# 11A-001.net
KiCad netlist of a schematic drawn in EAGLE
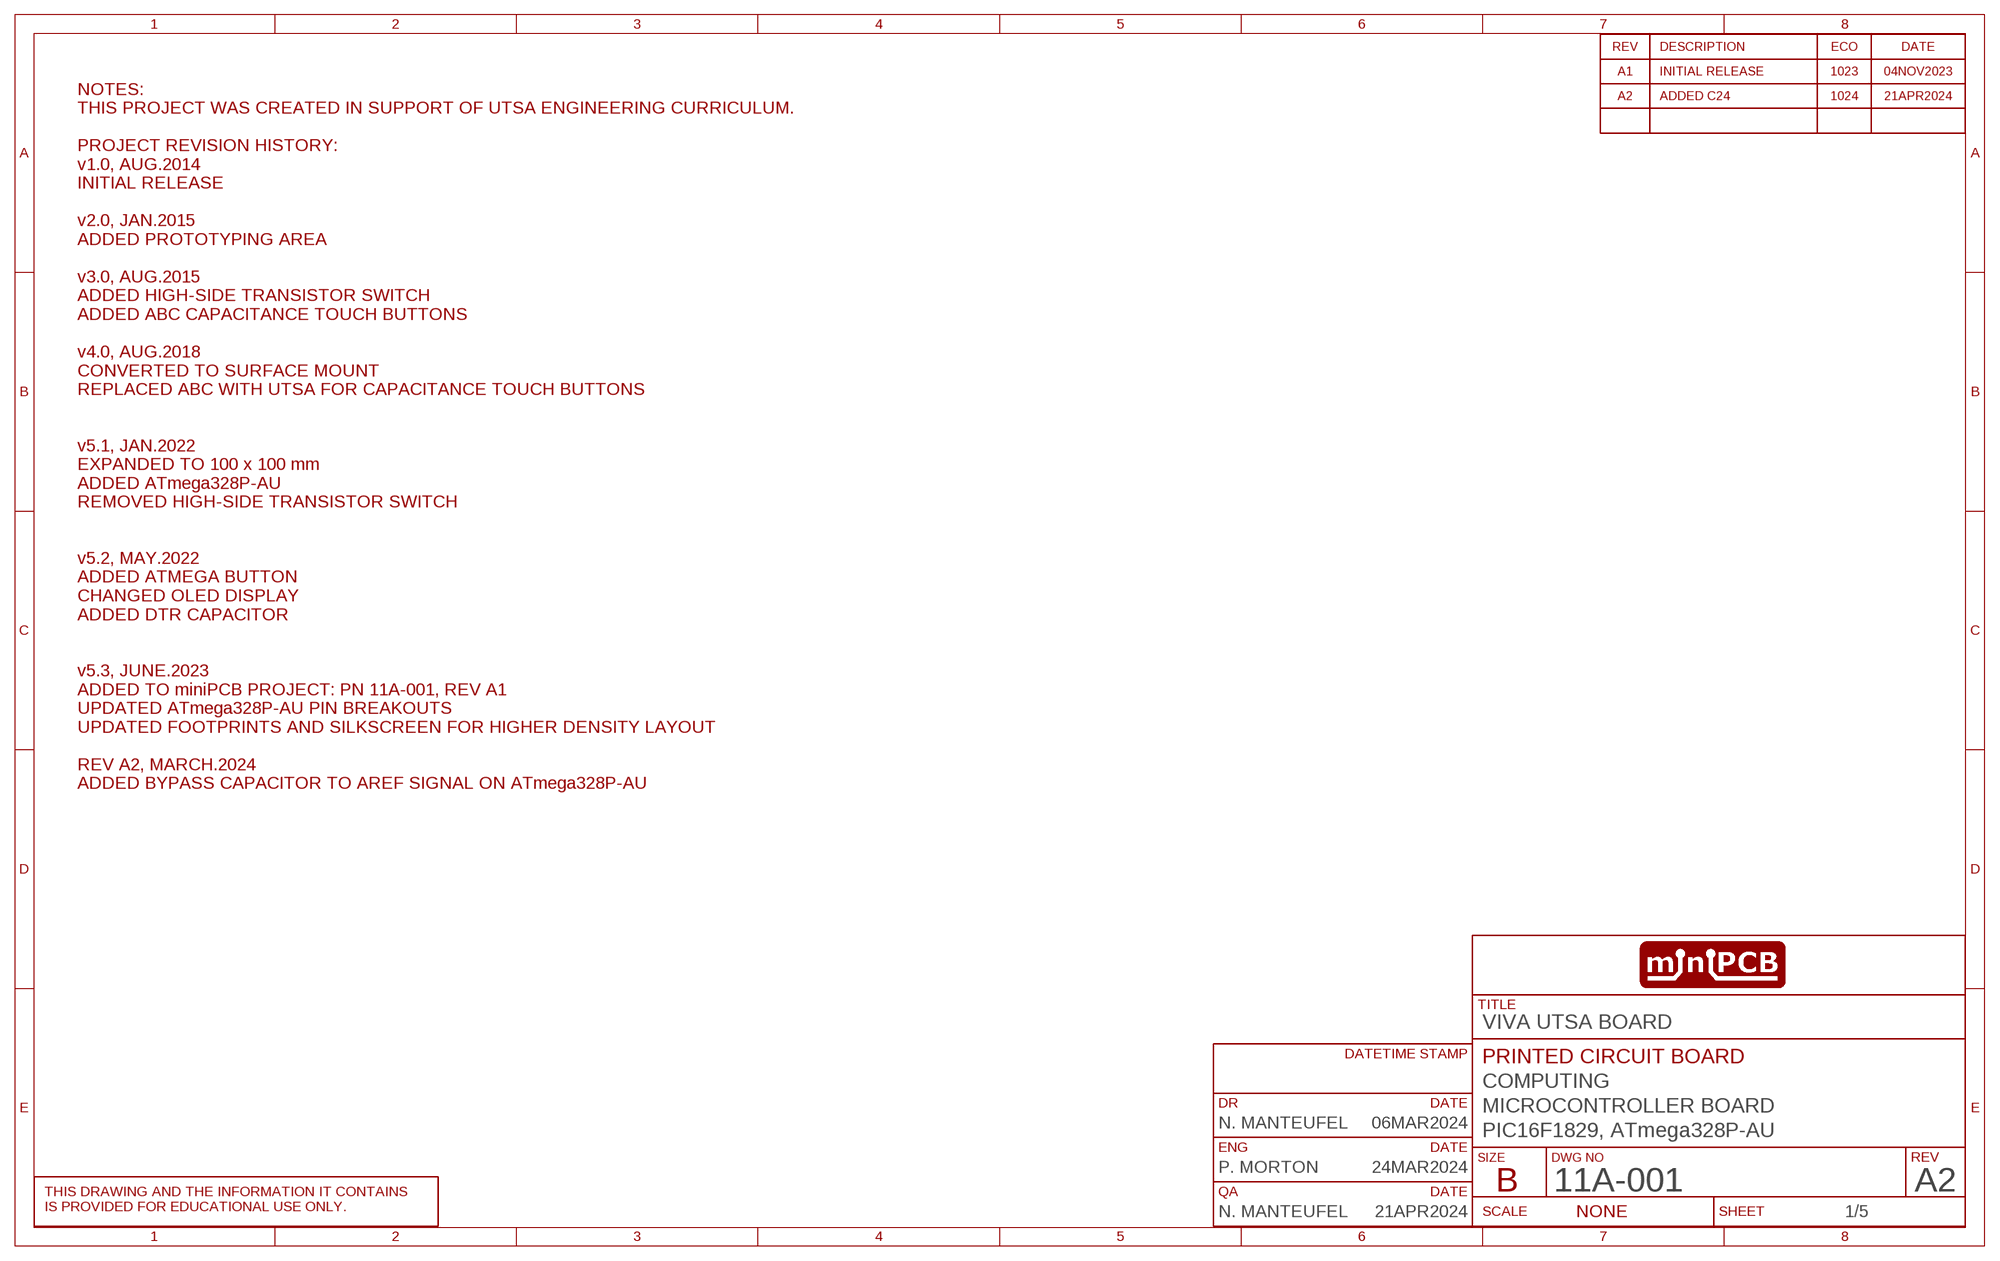
[diagram p0: schematic, sheet 1]
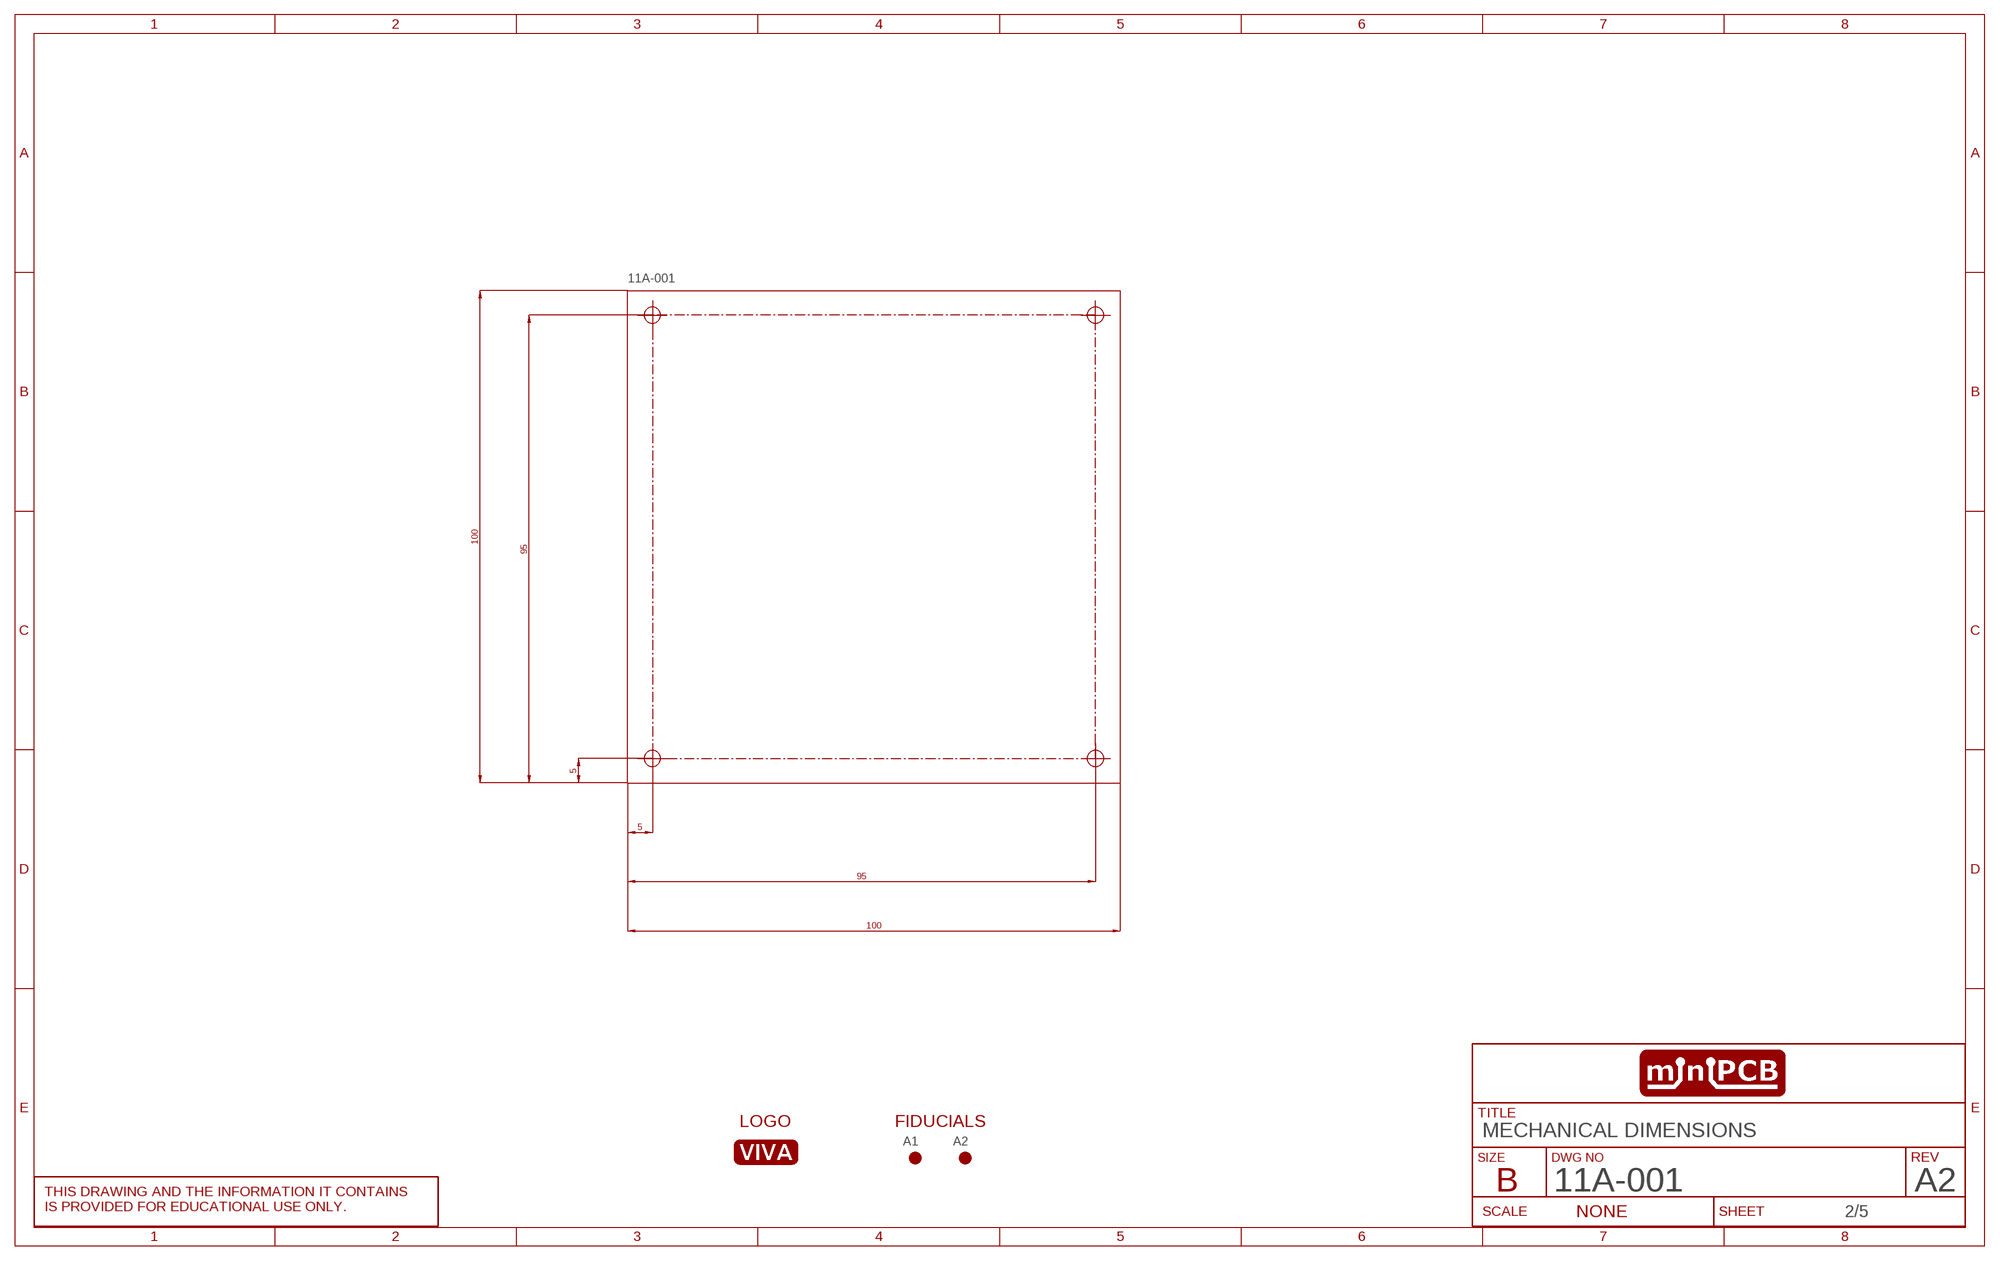
[diagram p1: schematic, sheet 2]
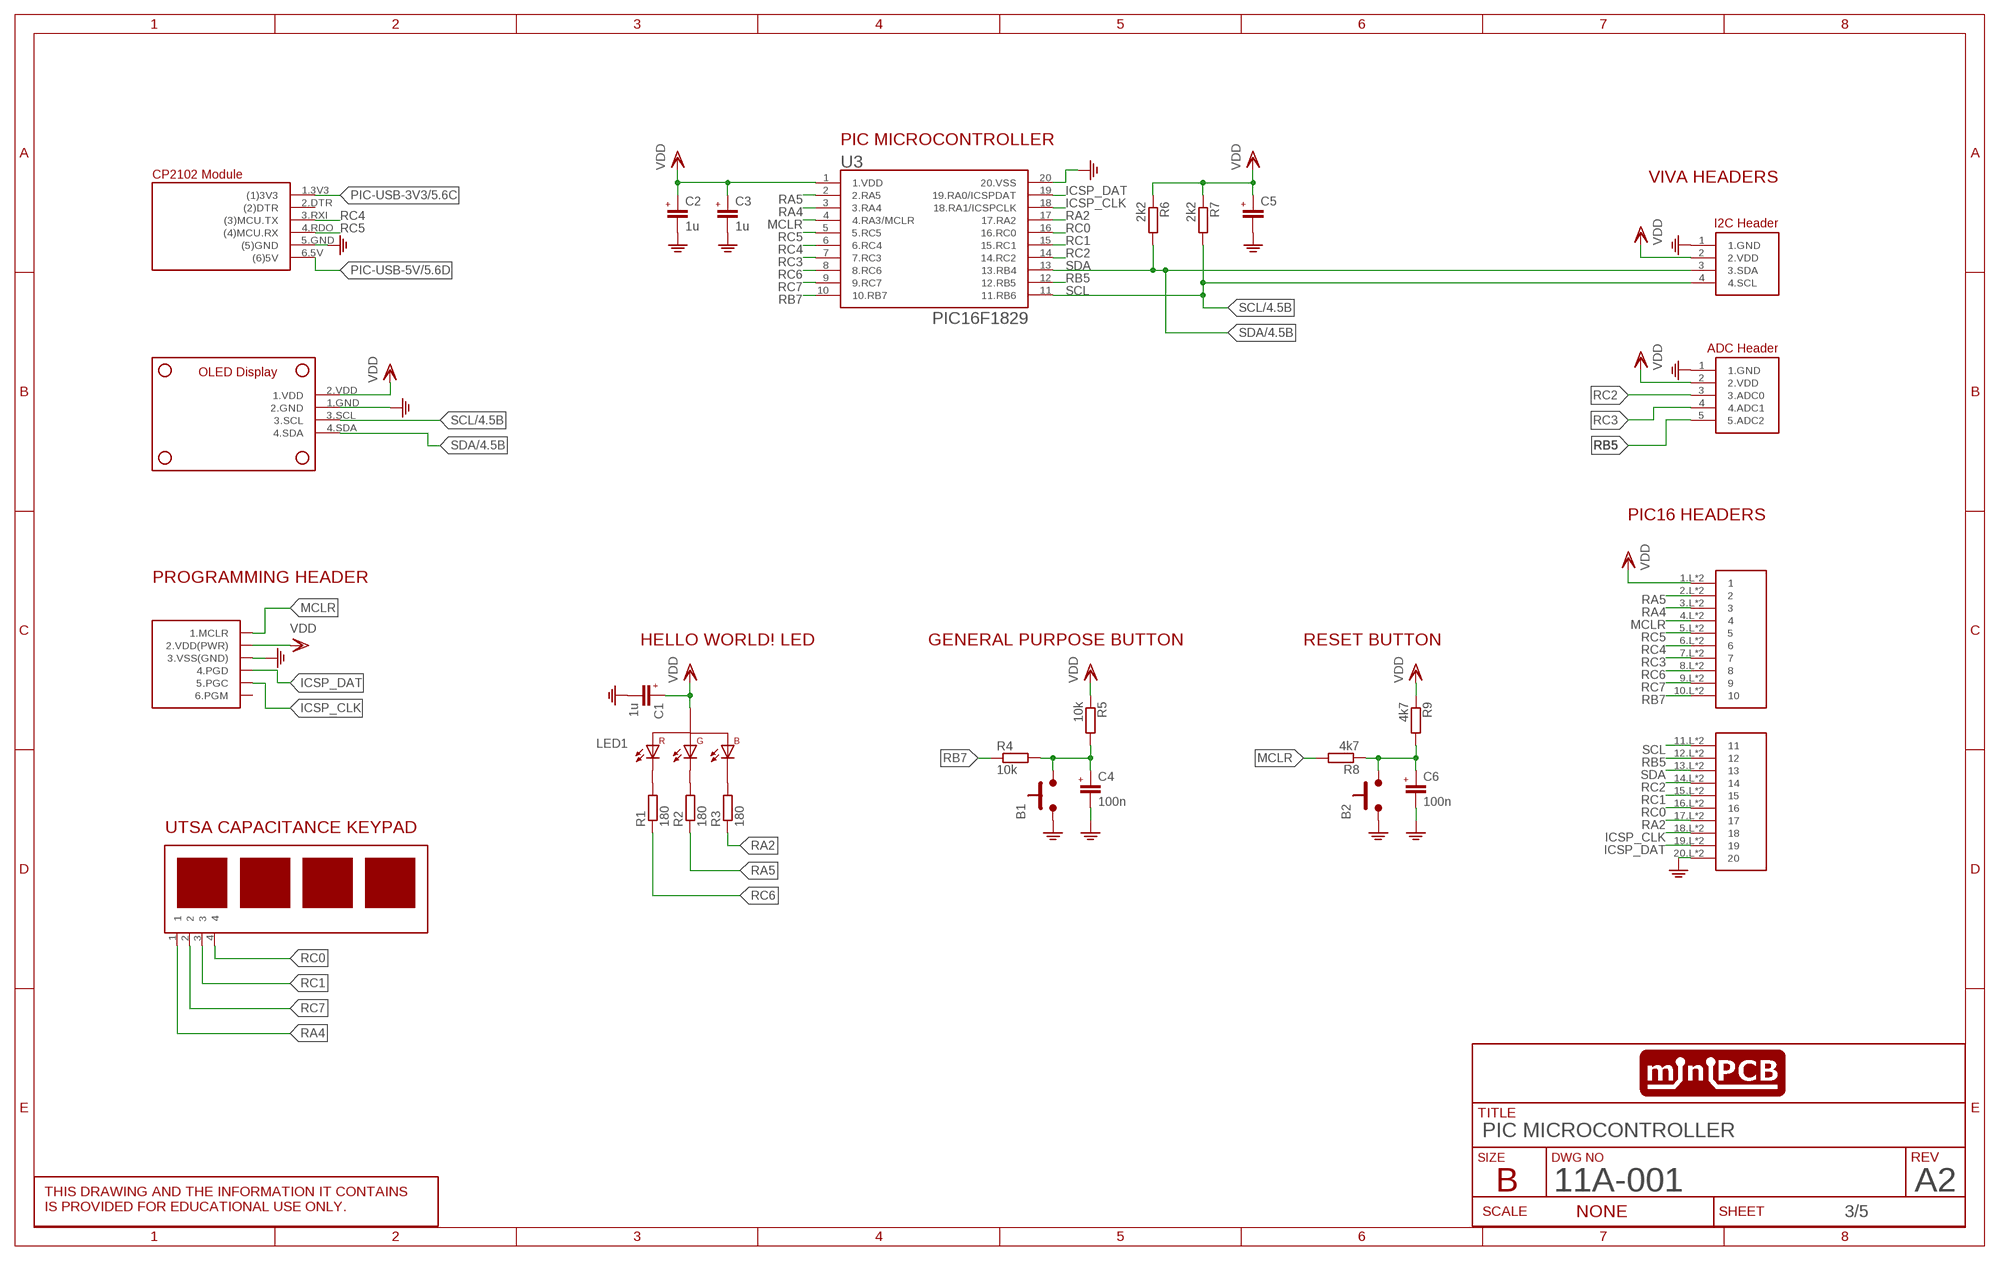
[diagram p2: schematic, sheet 3]
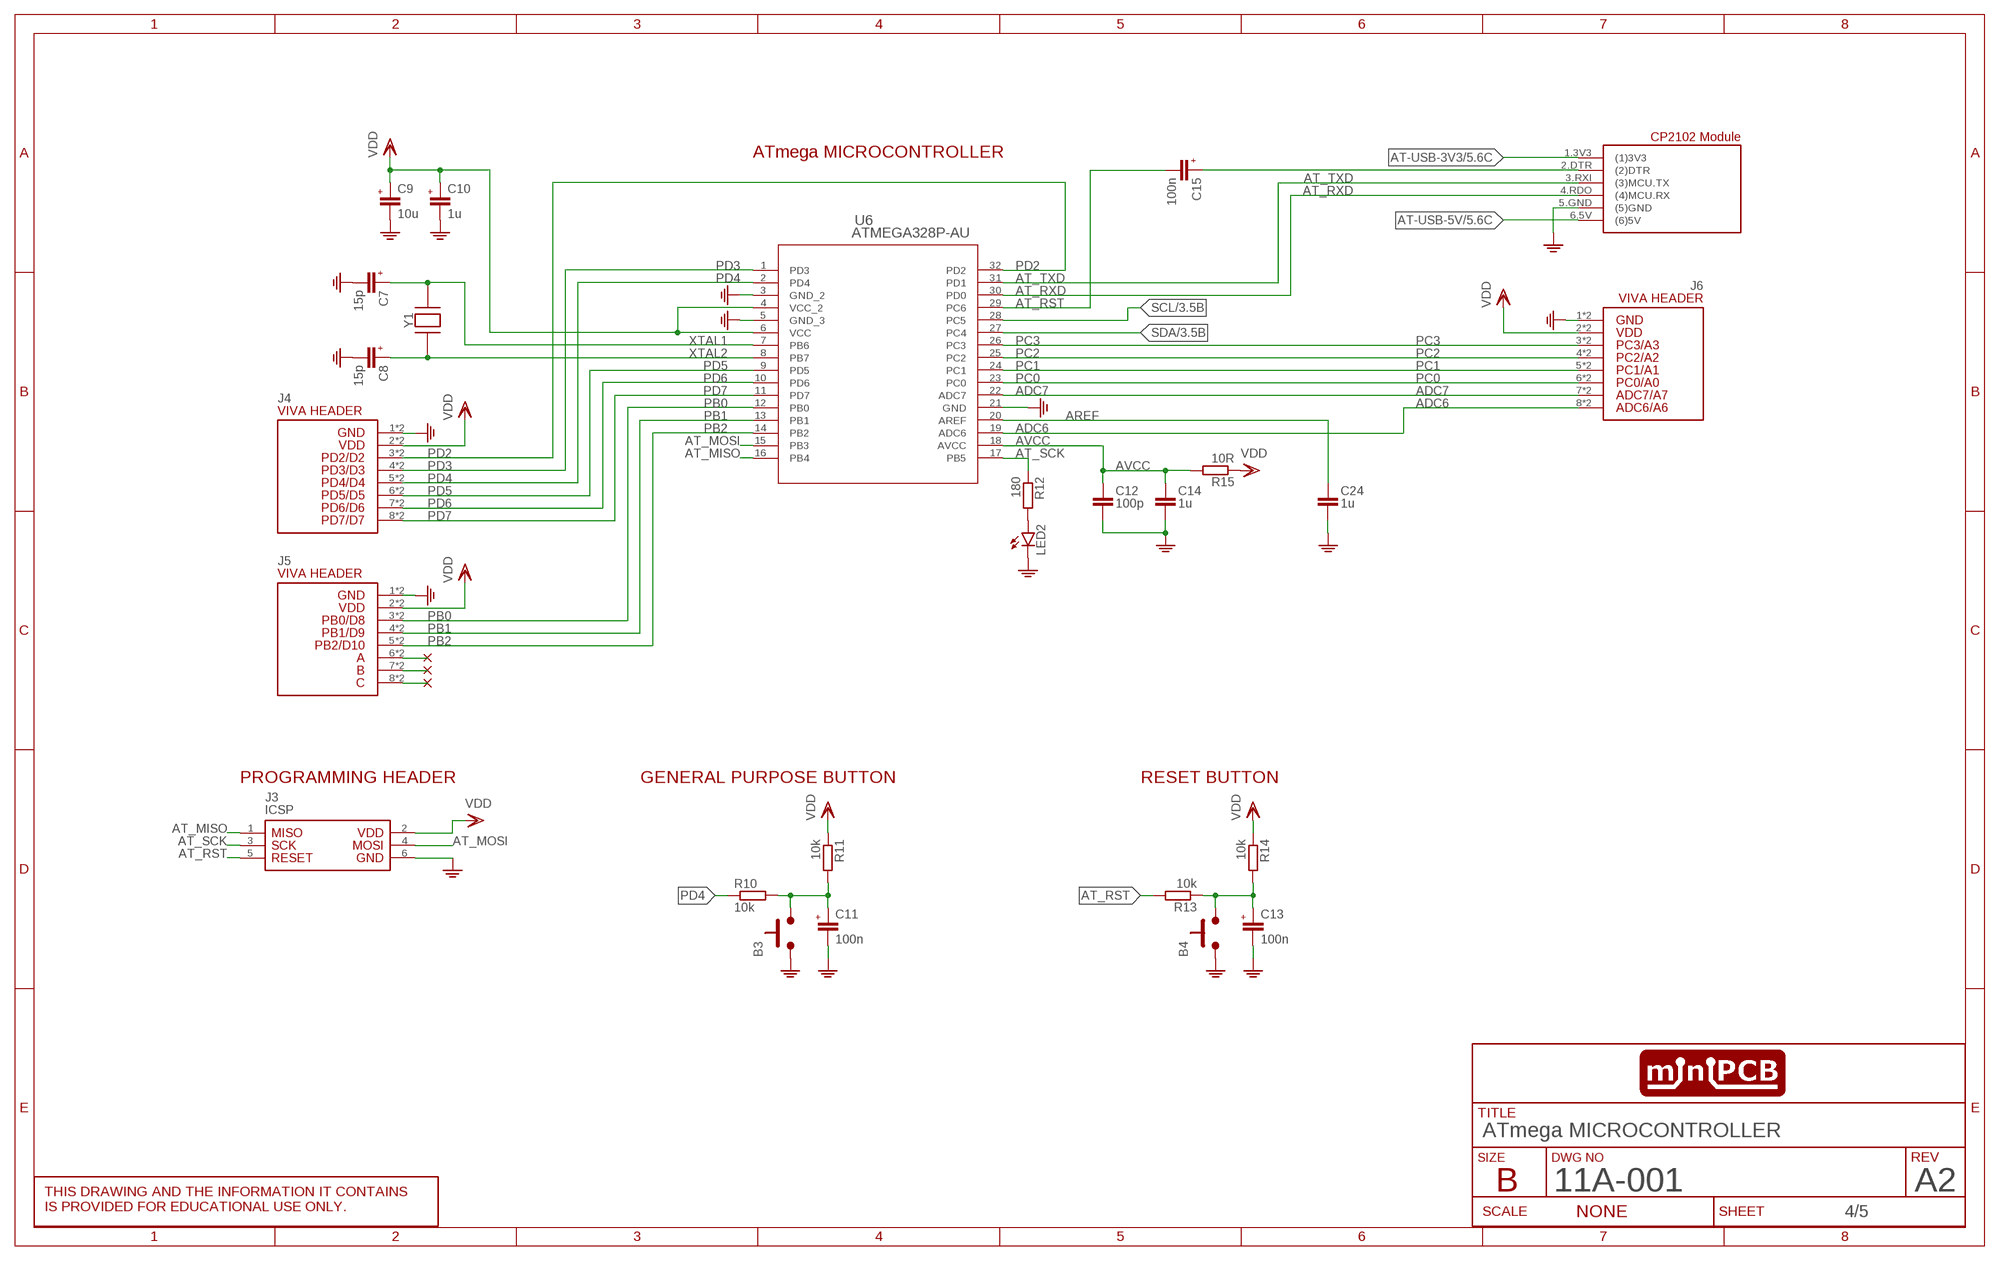
[diagram p3: schematic, sheet 4]
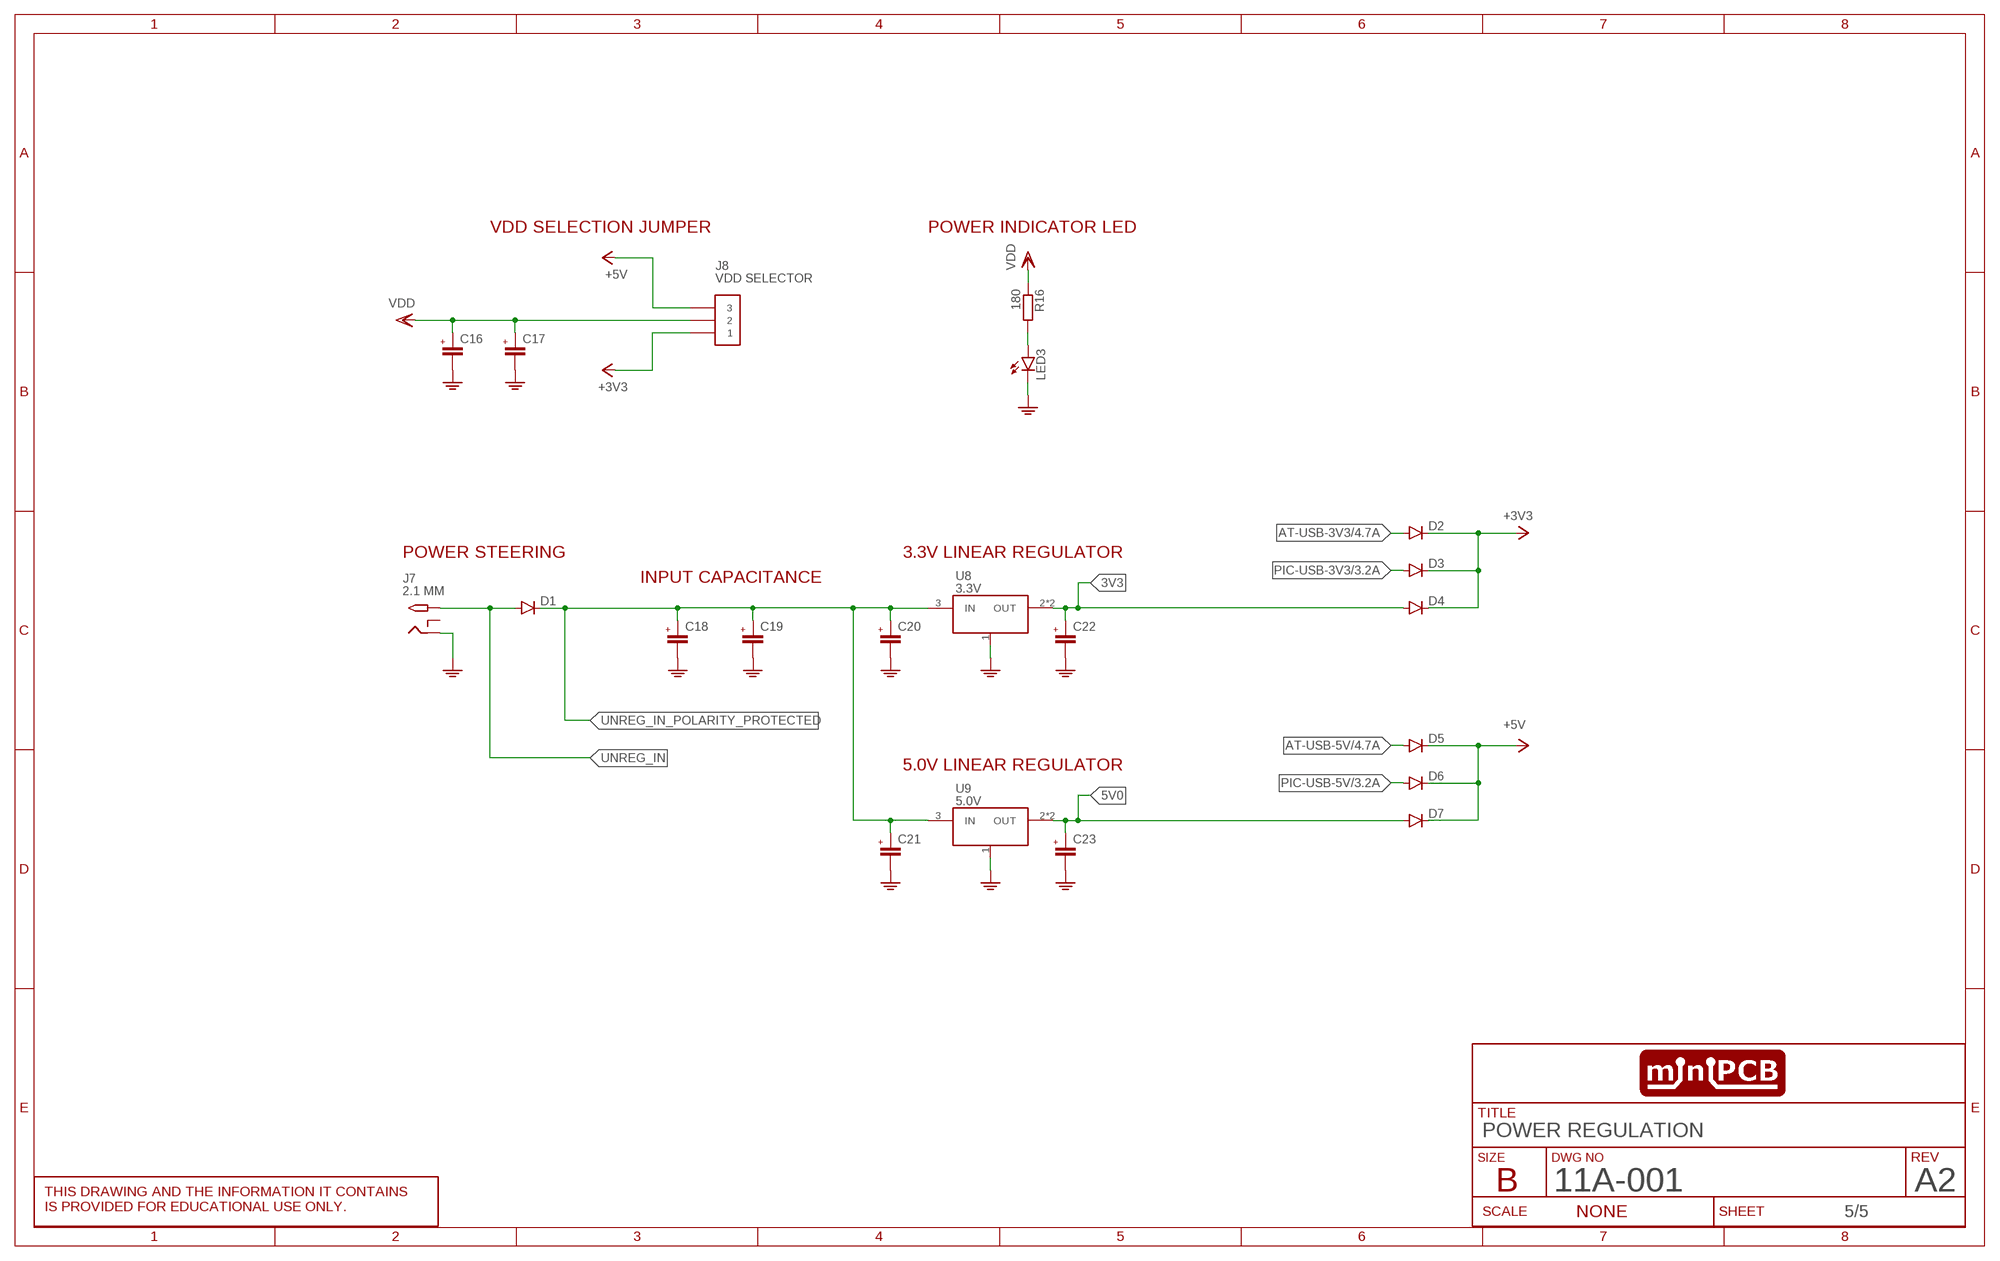
[diagram p4: schematic, sheet 5]

(export (version "E")
  (design (tool "Eeschema 10.0.6"))
  (components
    (comp (ref "B3")
      (value "PUSHBUTTON6X6MM")
      (footprint "eagle-import:6X6MM")
      (libsource (lib "eagle-import") (part "PUSHBUTTON6X6MM"))
    )
    (comp (ref "B4")
      (value "PUSHBUTTON6X6MM")
      (footprint "eagle-import:6X6MM")
      (libsource (lib "eagle-import") (part "PUSHBUTTON6X6MM"))
    )
    (comp (ref "C7")
      (value "15p")
      (footprint "eagle-import:C0603")
      (libsource (lib "eagle-import") (part "C0603"))
    )
    (comp (ref "C8")
      (value "15p")
      (footprint "eagle-import:C0603")
      (libsource (lib "eagle-import") (part "C0603"))
    )
    (comp (ref "C9")
      (value "10u")
      (footprint "eagle-import:C0805")
      (libsource (lib "eagle-import") (part "C0805"))
    )
    (comp (ref "C10")
      (value "1u")
      (footprint "eagle-import:C0805")
      (libsource (lib "eagle-import") (part "C0805"))
    )
    (comp (ref "C11")
      (value "100n")
      (footprint "eagle-import:C0805")
      (libsource (lib "eagle-import") (part "C0805"))
    )
    (comp (ref "C12")
      (value "100p")
      (footprint "eagle-import:C0805")
      (libsource (lib "eagle-import") (part "C-EU_C0805"))
    )
    (comp (ref "C13")
      (value "100n")
      (footprint "eagle-import:C0805")
      (libsource (lib "eagle-import") (part "C0805"))
    )
    (comp (ref "C14")
      (value "1u")
      (footprint "eagle-import:C0805")
      (libsource (lib "eagle-import") (part "C-EU_C0805"))
    )
    (comp (ref "C15")
      (value "100n")
      (footprint "eagle-import:C0805")
      (libsource (lib "eagle-import") (part "C0805"))
    )
    (comp (ref "C24")
      (value "1u")
      (footprint "eagle-import:C0805")
      (libsource (lib "eagle-import") (part "C-EU_C0805"))
    )
    (comp (ref "J3")
      (value "ICSP")
      (footprint "eagle-import:PINS_6-2X3_AT")
      (fields
        (field (name "P1") "P1 NAME")
        (field (name "P3") "P3 NAME")
        (field (name "P5") "P5 NAME")
        (field (name "P2") "P2 NAME")
        (field (name "P4") "P4 NAME")
        (field (name "P6") "P6 NAME")
        (field (name "P1_1") "MISO")
        (field (name "P2_1") "VDD")
        (field (name "P3_1") "SCK")
        (field (name "P4_1") "MOSI")
        (field (name "P5_1") "RESET")
        (field (name "P6_1") "GND")
      )
      (libsource (lib "eagle-import") (part "PINS_6-2X3_AT"))
    )
    (comp (ref "J4")
      (value "VIVA-HEADER-ADC-8P")
      (footprint "eagle-import:VIVA-HEADER-ADC-8P")
      (fields
        (field (name "P3") "P3 TEXT")
        (field (name "P4") "P4 TEXT")
        (field (name "P5") "P5 TEXT")
        (field (name "P6") "P6 TEXT")
        (field (name "P7") "P7 TEXT")
        (field (name "P8") "P8 TEXT")
        (field (name "P3_1") "PD2/D2")
        (field (name "P4_1") "PD3/D3")
        (field (name "P5_1") "PD4/D4")
        (field (name "P6_1") "PD5/D5")
        (field (name "P7_1") "PD6/D6")
        (field (name "P8_1") "PD7/D7")
      )
      (libsource (lib "eagle-import") (part "VIVA-HEADER-ADC-8P"))
    )
    (comp (ref "J5")
      (value "VIVA-HEADER-ADC-8P")
      (footprint "eagle-import:VIVA-HEADER-ADC-8P")
      (fields
        (field (name "P3") "P3 TEXT")
        (field (name "P4") "P4 TEXT")
        (field (name "P5") "P5 TEXT")
        (field (name "P6") "P6 TEXT")
        (field (name "P7") "P7 TEXT")
        (field (name "P8") "P8 TEXT")
        (field (name "P3_1") "PB0/D8")
        (field (name "P4_1") "PB1/D9")
        (field (name "P5_1") "PB2/D10")
        (field (name "P6_1") "A")
        (field (name "P7_1") "B")
        (field (name "P8_1") "C")
      )
      (libsource (lib "eagle-import") (part "VIVA-HEADER-ADC-8P"))
    )
    (comp (ref "J6")
      (value "VIVA-HEADER-ADC-8P")
      (footprint "eagle-import:VIVA-HEADER-ADC-8P")
      (fields
        (field (name "P3") "P3 TEXT")
        (field (name "P4") "P4 TEXT")
        (field (name "P5") "P5 TEXT")
        (field (name "P6") "P6 TEXT")
        (field (name "P7") "P7 TEXT")
        (field (name "P8") "P8 TEXT")
        (field (name "P3_1") "PC3/A3")
        (field (name "P4_1") "PC2/A2")
        (field (name "P5_1") "PC1/A1")
        (field (name "P6_1") "PC0/A0")
        (field (name "P7_1") "ADC7/A7")
        (field (name "P8_1") "ADC6/A6")
      )
      (libsource (lib "eagle-import") (part "VIVA-HEADER-ADC-8P"))
    )
    (comp (ref "LED2")
      (value "LEDSML0805")
      (footprint "eagle-import:SML0805")
      (libsource (lib "eagle-import") (part "LEDSML0805"))
    )
    (comp (ref "R10")
      (value "10k")
      (footprint "eagle-import:R0805")
      (libsource (lib "eagle-import") (part "R-EU__R0805"))
    )
    (comp (ref "R11")
      (value "10k")
      (footprint "eagle-import:R0805")
      (libsource (lib "eagle-import") (part "R-EU__R0805"))
    )
    (comp (ref "R12")
      (value "180")
      (footprint "eagle-import:R0805")
      (libsource (lib "eagle-import") (part "R-EU__R0805"))
    )
    (comp (ref "R13")
      (value "10k")
      (footprint "eagle-import:R0805")
      (libsource (lib "eagle-import") (part "R-EU__R0805"))
    )
    (comp (ref "R14")
      (value "10k")
      (footprint "eagle-import:R0805")
      (libsource (lib "eagle-import") (part "R-EU__R0805"))
    )
    (comp (ref "R15")
      (value "10R")
      (footprint "eagle-import:R0805")
      (libsource (lib "eagle-import") (part "R-EU__R0805"))
    )
    (comp (ref "U6")
      (value "ATMEGA328P-AU")
      (footprint "eagle-import:32A_ATM")
      (fields
        (field (name "MANUFACTURER_PART_NUMBER") "ATMEGA328-AU")
        (field (name "COPYRIGHT") "Copyright (C) 2021 Ultra Librarian. All rights reserved.")
      )
      (libsource (lib "eagle-import") (part "ATMEGA328-AU"))
    )
    (comp (ref "U7")
      (value "VIVA_USB-TTL")
      (footprint "eagle-import:VIVA_USB_TTL_SUBTEXT")
      (libsource (lib "eagle-import") (part "VIVA_USB-TTL"))
    )
    (comp (ref "Y1")
      (value "CRYSTAL-3225_4P")
      (footprint "eagle-import:TXC7M2")
      (libsource (lib "eagle-import") (part "CRYSTAL-3225_4P"))
    )
    (comp (ref "-")
      (value "11A-001")
      (footprint "eagle-import:PCB_100X100")
      (libsource (lib "eagle-import") (part "PCB_100X100"))
    )
    (comp (ref "A1")
      (value "FIDUCIAL")
      (footprint "eagle-import:FIDUCIAL")
      (libsource (lib "eagle-import") (part "FIDUCIAL"))
    )
    (comp (ref "A2")
      (value "FIDUCIAL")
      (footprint "eagle-import:FIDUCIAL")
      (libsource (lib "eagle-import") (part "FIDUCIAL"))
    )
    (comp (ref "U$2")
      (value "VIVA_LOGO")
      (footprint "eagle-import:VIVA_LOGO")
      (libsource (lib "eagle-import") (part "VIVA_LOGO"))
    )
    (comp (ref "C16")
      (value "C0805")
      (footprint "eagle-import:C0805")
      (libsource (lib "eagle-import") (part "C0805"))
    )
    (comp (ref "C17")
      (value "C0805")
      (footprint "eagle-import:C0805")
      (libsource (lib "eagle-import") (part "C0805"))
    )
    (comp (ref "C18")
      (value "C0805")
      (footprint "eagle-import:C0805")
      (libsource (lib "eagle-import") (part "C0805"))
    )
    (comp (ref "C19")
      (value "C0805")
      (footprint "eagle-import:C0805")
      (libsource (lib "eagle-import") (part "C0805"))
    )
    (comp (ref "C20")
      (value "C0805")
      (footprint "eagle-import:C0805")
      (libsource (lib "eagle-import") (part "C0805"))
    )
    (comp (ref "C21")
      (value "C0805")
      (footprint "eagle-import:C0805")
      (libsource (lib "eagle-import") (part "C0805"))
    )
    (comp (ref "C22")
      (value "C0805")
      (footprint "eagle-import:C0805")
      (libsource (lib "eagle-import") (part "C0805"))
    )
    (comp (ref "C23")
      (value "C0805")
      (footprint "eagle-import:C0805")
      (libsource (lib "eagle-import") (part "C0805"))
    )
    (comp (ref "D1")
      (value "DIODE-DO214AC")
      (footprint "eagle-import:DO214AC")
      (libsource (lib "eagle-import") (part "DIODE-DO214AC"))
    )
    (comp (ref "D2")
      (value "DIODE-DO214AC")
      (footprint "eagle-import:DO214AC")
      (libsource (lib "eagle-import") (part "DIODE-DO214AC"))
    )
    (comp (ref "D3")
      (value "DIODE-DO214AC")
      (footprint "eagle-import:DO214AC")
      (libsource (lib "eagle-import") (part "DIODE-DO214AC"))
    )
    (comp (ref "D4")
      (value "DIODE-DO214AC")
      (footprint "eagle-import:DO214AC")
      (libsource (lib "eagle-import") (part "DIODE-DO214AC"))
    )
    (comp (ref "D5")
      (value "DIODE-DO214AC")
      (footprint "eagle-import:DO214AC")
      (libsource (lib "eagle-import") (part "DIODE-DO214AC"))
    )
    (comp (ref "D6")
      (value "DIODE-DO214AC")
      (footprint "eagle-import:DO214AC")
      (libsource (lib "eagle-import") (part "DIODE-DO214AC"))
    )
    (comp (ref "D7")
      (value "DIODE-DO214AC")
      (footprint "eagle-import:DO214AC")
      (libsource (lib "eagle-import") (part "DIODE-DO214AC"))
    )
    (comp (ref "J7")
      (value "2.1 MM")
      (footprint "eagle-import:PJ-102A")
      (libsource (lib "eagle-import") (part "2.1MMJACKTHM"))
    )
    (comp (ref "J8")
      (value "VDD SELECTOR")
      (footprint "eagle-import:PINS_3")
      (libsource (lib "eagle-import") (part "PINS_3_2.54"))
    )
    (comp (ref "LED3")
      (value "LEDSML0805")
      (footprint "eagle-import:SML0805")
      (libsource (lib "eagle-import") (part "LEDSML0805"))
    )
    (comp (ref "R16")
      (value "180")
      (footprint "eagle-import:R0805")
      (libsource (lib "eagle-import") (part "R-EU__R0805"))
    )
    (comp (ref "U8")
      (value "3.3V")
      (footprint "eagle-import:SOT223")
      (libsource (lib "eagle-import") (part "REGULATOR_SCHLM1117"))
    )
    (comp (ref "U9")
      (value "5.0V")
      (footprint "eagle-import:SOT223")
      (libsource (lib "eagle-import") (part "REGULATOR_SCHLM1117"))
    )
    (comp (ref "$3_73_$")
      (value "VIVA_OLEDGND")
      (footprint "eagle-import:VIVA_OLED-I2C-ALT")
      (libsource (lib "eagle-import") (part "VIVA_OLEDGND"))
    )
    (comp (ref "B1")
      (value "PUSHBUTTON6X6MM")
      (footprint "eagle-import:6X6MM")
      (libsource (lib "eagle-import") (part "PUSHBUTTON6X6MM"))
    )
    (comp (ref "B2")
      (value "PUSHBUTTON6X6MM")
      (footprint "eagle-import:6X6MM")
      (libsource (lib "eagle-import") (part "PUSHBUTTON6X6MM"))
    )
    (comp (ref "C1")
      (value "1u")
      (footprint "eagle-import:C0805")
      (libsource (lib "eagle-import") (part "C0805"))
    )
    (comp (ref "C2")
      (value "1u")
      (footprint "eagle-import:C0805")
      (libsource (lib "eagle-import") (part "C0805"))
    )
    (comp (ref "C3")
      (value "1u")
      (footprint "eagle-import:C0805")
      (libsource (lib "eagle-import") (part "C0805"))
    )
    (comp (ref "C4")
      (value "100n")
      (footprint "eagle-import:C0805")
      (libsource (lib "eagle-import") (part "C0805"))
    )
    (comp (ref "C5")
      (value "C0805")
      (footprint "eagle-import:C0805")
      (libsource (lib "eagle-import") (part "C0805"))
    )
    (comp (ref "C6")
      (value "100n")
      (footprint "eagle-import:C0805")
      (libsource (lib "eagle-import") (part "C0805"))
    )
    (comp (ref "J1")
      (value "PICKIT3")
      (footprint "eagle-import:PICKIT3")
      (libsource (lib "eagle-import") (part "PICKIT3"))
    )
    (comp (ref "J2")
      (value "VIVA-HEADER-ADC-PIC16")
      (footprint "eagle-import:VIVA-HEADER-ADC-PIC16")
      (libsource (lib "eagle-import") (part "VIVA-HEADER-ADC-PIC16"))
    )
    (comp (ref "LED1")
      (value "LED_RGBLTST-C19FD1WT")
      (footprint "eagle-import:0805_RGB")
      (libsource (lib "eagle-import") (part "LED_RGBLTST-C19FD1WT"))
    )
    (comp (ref "R1")
      (value "180")
      (footprint "eagle-import:R0805")
      (libsource (lib "eagle-import") (part "R-EU__R0805"))
    )
    (comp (ref "R2")
      (value "180")
      (footprint "eagle-import:R0805")
      (libsource (lib "eagle-import") (part "R-EU__R0805"))
    )
    (comp (ref "R3")
      (value "180")
      (footprint "eagle-import:R0805")
      (libsource (lib "eagle-import") (part "R-EU__R0805"))
    )
    (comp (ref "R4")
      (value "10k")
      (footprint "eagle-import:R0805")
      (libsource (lib "eagle-import") (part "R-EU__R0805"))
    )
    (comp (ref "R5")
      (value "10k")
      (footprint "eagle-import:R0805")
      (libsource (lib "eagle-import") (part "R-EU__R0805"))
    )
    (comp (ref "R6")
      (value "2k2")
      (footprint "eagle-import:R0805")
      (libsource (lib "eagle-import") (part "R-EU__R0805"))
    )
    (comp (ref "R7")
      (value "2k2")
      (footprint "eagle-import:R0805")
      (libsource (lib "eagle-import") (part "R-EU__R0805"))
    )
    (comp (ref "R8")
      (value "4k7")
      (footprint "eagle-import:R0805")
      (libsource (lib "eagle-import") (part "R-EU__R0805"))
    )
    (comp (ref "R9")
      (value "4k7")
      (footprint "eagle-import:R0805")
      (libsource (lib "eagle-import") (part "R-EU__R0805"))
    )
    (comp (ref "U1")
      (value "VIVA_UTSA-KEYPADV5")
      (footprint "eagle-import:VIVA_UTSA-KEYPAD-V5")
      (libsource (lib "eagle-import") (part "VIVA_UTSA-KEYPADV5"))
    )
    (comp (ref "U2")
      (value "VIVA_USB-TTL")
      (footprint "eagle-import:VIVA_USB_TTL_SUBTEXT")
      (libsource (lib "eagle-import") (part "VIVA_USB-TTL"))
    )
    (comp (ref "U3")
      (value "PIC16F1829")
      (footprint "eagle-import:SOP20-NEW")
      (libsource (lib "eagle-import") (part "PIC16F1829300"))
    )
    (comp (ref "U4")
      (value "VIVA-HEADER-I2C-RA")
      (footprint "eagle-import:VIVA-HEADER-I2C-RA")
      (libsource (lib "eagle-import") (part "VIVA-HEADER-I2C-RA"))
    )
    (comp (ref "U5")
      (value "VIVA_PIC16BOARD")
      (footprint "eagle-import:VIVA_PIC16")
      (libsource (lib "eagle-import") (part "VIVA_PIC16BOARD"))
    )
  )
  (nets
    (net (code "1") (name "+3V3") (class "Default")
      (node (ref "D2") (pin "C") (pinfunction "C_C") (pintype "passive"))
      (node (ref "D3") (pin "C") (pinfunction "C_C") (pintype "passive"))
      (node (ref "D4") (pin "C") (pinfunction "C_C") (pintype "passive"))
      (node (ref "J8") (pin "1") (pinfunction "1_1") (pintype "bidirectional"))
    )
    (net (code "2") (name "+5V") (class "Default")
      (node (ref "D5") (pin "C") (pinfunction "C_C") (pintype "passive"))
      (node (ref "D6") (pin "C") (pinfunction "C_C") (pintype "passive"))
      (node (ref "D7") (pin "C") (pinfunction "C_C") (pintype "passive"))
      (node (ref "J8") (pin "3") (pinfunction "3_3") (pintype "bidirectional"))
    )
    (net (code "3") (name "3V3") (class "Default")
      (node (ref "C22") (pin "1") (pinfunction "+_1") (pintype "passive"))
      (node (ref "D4") (pin "A") (pinfunction "A_A") (pintype "passive"))
      (node (ref "U8") (pin "2") (pinfunction "OUT_2") (pintype "bidirectional"))
      (node (ref "U8") (pin "4.TAB") (pinfunction "OUT_4.TAB") (pintype "bidirectional"))
    )
    (net (code "4") (name "5V0") (class "Default")
      (node (ref "C23") (pin "1") (pinfunction "+_1") (pintype "passive"))
      (node (ref "D7") (pin "A") (pinfunction "A_A") (pintype "passive"))
      (node (ref "U9") (pin "2") (pinfunction "OUT_2") (pintype "bidirectional"))
      (node (ref "U9") (pin "4.TAB") (pinfunction "OUT_4.TAB") (pintype "bidirectional"))
    )
    (net (code "5") (name "ADC6") (class "Default")
      (node (ref "J6") (pin "8") (pinfunction "8.ADC5_8") (pintype "bidirectional"))
      (node (ref "J6") (pin "9") (pinfunction "8.ADC5_9") (pintype "bidirectional"))
      (node (ref "U6") (pin "19") (pinfunction "ADC6_19") (pintype "passive"))
    )
    (net (code "6") (name "ADC7") (class "Default")
      (node (ref "J6") (pin "10") (pinfunction "7.ADC4_10") (pintype "bidirectional"))
      (node (ref "J6") (pin "7") (pinfunction "7.ADC4_7") (pintype "bidirectional"))
      (node (ref "U6") (pin "22") (pinfunction "ADC7_22") (pintype "passive"))
    )
    (net (code "7") (name "AREF") (class "Default")
      (node (ref "C24") (pin "1") (pinfunction "1_1") (pintype "passive"))
      (node (ref "U6") (pin "20") (pinfunction "AREF_20") (pintype "passive"))
    )
    (net (code "8") (name "AT-USB-3V3") (class "Default")
      (node (ref "D2") (pin "A") (pinfunction "A_A") (pintype "passive"))
      (node (ref "U7") (pin "1.3V3") (pinfunction "(1)3V3_1.3V3") (pintype "bidirectional"))
    )
    (net (code "9") (name "AT-USB-5V") (class "Default")
      (node (ref "D5") (pin "A") (pinfunction "A_A") (pintype "passive"))
      (node (ref "U7") (pin "6.5V") (pinfunction "(6)5V_6.5V") (pintype "bidirectional"))
    )
    (net (code "10") (name "AT_MISO") (class "Default")
      (node (ref "J3") (pin "1") (pinfunction "1_1") (pintype "bidirectional"))
      (node (ref "U6") (pin "16") (pinfunction "PB4_16") (pintype "bidirectional"))
    )
    (net (code "11") (name "AT_MOSI") (class "Default")
      (node (ref "J3") (pin "4") (pinfunction "4_4") (pintype "bidirectional"))
      (node (ref "U6") (pin "15") (pinfunction "PB3_15") (pintype "bidirectional"))
    )
    (net (code "12") (name "AT_RST") (class "Default")
      (node (ref "C15") (pin "2") (pinfunction "-_2") (pintype "passive"))
      (node (ref "J3") (pin "5") (pinfunction "5_5") (pintype "bidirectional"))
      (node (ref "R13") (pin "2") (pinfunction "2_2") (pintype "passive"))
      (node (ref "U6") (pin "29") (pinfunction "PC6_29") (pintype "bidirectional"))
    )
    (net (code "13") (name "AT_RXD") (class "Default")
      (node (ref "U6") (pin "30") (pinfunction "PD0_30") (pintype "bidirectional"))
      (node (ref "U7") (pin "4.RDO") (pinfunction "(4)MCU.RX_4.RDO") (pintype "bidirectional"))
    )
    (net (code "14") (name "AT_SCK") (class "Default")
      (node (ref "J3") (pin "3") (pinfunction "3_3") (pintype "bidirectional"))
      (node (ref "R12") (pin "1") (pinfunction "1_1") (pintype "passive"))
      (node (ref "U6") (pin "17") (pinfunction "PB5_17") (pintype "bidirectional"))
    )
    (net (code "15") (name "AT_TXD") (class "Default")
      (node (ref "U6") (pin "31") (pinfunction "PD1_31") (pintype "bidirectional"))
      (node (ref "U7") (pin "3.RXI") (pinfunction "(3)MCU.TX_3.RXI") (pintype "bidirectional"))
    )
    (net (code "16") (name "AVCC") (class "Default")
      (node (ref "C12") (pin "1") (pinfunction "1_1") (pintype "passive"))
      (node (ref "C14") (pin "1") (pinfunction "1_1") (pintype "passive"))
      (node (ref "R15") (pin "2") (pinfunction "2_2") (pintype "passive"))
      (node (ref "U6") (pin "18") (pinfunction "AVCC_18") (pintype "power_in"))
    )
    (net (code "17") (name "GND") (class "Default")
      (node (ref "$3_73_$") (pin "1.GND") (pinfunction "2.GND_1.GND") (pintype "bidirectional"))
      (node (ref "B1") (pin "1.A") (pinfunction "1_1.A") (pintype "bidirectional"))
      (node (ref "B1") (pin "2.A") (pinfunction "1_2.A") (pintype "bidirectional"))
      (node (ref "B2") (pin "1.A") (pinfunction "1_1.A") (pintype "bidirectional"))
      (node (ref "B2") (pin "2.A") (pinfunction "1_2.A") (pintype "bidirectional"))
      (node (ref "B3") (pin "1.A") (pinfunction "1_1.A") (pintype "bidirectional"))
      (node (ref "B3") (pin "2.A") (pinfunction "1_2.A") (pintype "bidirectional"))
      (node (ref "B4") (pin "1.A") (pinfunction "1_1.A") (pintype "bidirectional"))
      (node (ref "B4") (pin "2.A") (pinfunction "1_2.A") (pintype "bidirectional"))
      (node (ref "C1") (pin "2") (pinfunction "-_2") (pintype "passive"))
      (node (ref "C10") (pin "2") (pinfunction "-_2") (pintype "passive"))
      (node (ref "C11") (pin "2") (pinfunction "-_2") (pintype "passive"))
      (node (ref "C12") (pin "2") (pinfunction "2_2") (pintype "passive"))
      (node (ref "C13") (pin "2") (pinfunction "-_2") (pintype "passive"))
      (node (ref "C14") (pin "2") (pinfunction "2_2") (pintype "passive"))
      (node (ref "C16") (pin "2") (pinfunction "-_2") (pintype "passive"))
      (node (ref "C17") (pin "2") (pinfunction "-_2") (pintype "passive"))
      (node (ref "C18") (pin "2") (pinfunction "-_2") (pintype "passive"))
      (node (ref "C19") (pin "2") (pinfunction "-_2") (pintype "passive"))
      (node (ref "C2") (pin "2") (pinfunction "-_2") (pintype "passive"))
      (node (ref "C20") (pin "2") (pinfunction "-_2") (pintype "passive"))
      (node (ref "C21") (pin "2") (pinfunction "-_2") (pintype "passive"))
      (node (ref "C22") (pin "2") (pinfunction "-_2") (pintype "passive"))
      (node (ref "C23") (pin "2") (pinfunction "-_2") (pintype "passive"))
      (node (ref "C24") (pin "2") (pinfunction "2_2") (pintype "passive"))
      (node (ref "C3") (pin "2") (pinfunction "-_2") (pintype "passive"))
      (node (ref "C4") (pin "2") (pinfunction "-_2") (pintype "passive"))
      (node (ref "C5") (pin "2") (pinfunction "-_2") (pintype "passive"))
      (node (ref "C6") (pin "2") (pinfunction "-_2") (pintype "passive"))
      (node (ref "C7") (pin "1") (pinfunction "-_1") (pintype "passive"))
      (node (ref "C8") (pin "1") (pinfunction "-_1") (pintype "passive"))
      (node (ref "C9") (pin "2") (pinfunction "-_2") (pintype "passive"))
      (node (ref "J1") (pin "3") (pinfunction "3.VSS(GND)_3") (pintype "bidirectional"))
      (node (ref "J2") (pin "1") (pinfunction "1.GND_1") (pintype "bidirectional"))
      (node (ref "J3") (pin "6") (pinfunction "6_6") (pintype "bidirectional"))
      (node (ref "J4") (pin "1") (pinfunction "1.GND_1") (pintype "bidirectional"))
      (node (ref "J4") (pin "16") (pinfunction "1.GND_16") (pintype "bidirectional"))
      (node (ref "J5") (pin "1") (pinfunction "1.GND_1") (pintype "bidirectional"))
      (node (ref "J5") (pin "16") (pinfunction "1.GND_16") (pintype "bidirectional"))
      (node (ref "J6") (pin "1") (pinfunction "1.GND_1") (pintype "bidirectional"))
      (node (ref "J6") (pin "16") (pinfunction "1.GND_16") (pintype "bidirectional"))
      (node (ref "J7") (pin "RING") (pinfunction "RING_RING") (pintype "bidirectional"))
      (node (ref "LED2") (pin "C") (pinfunction "C_C") (pintype "passive"))
      (node (ref "LED3") (pin "C") (pinfunction "C_C") (pintype "passive"))
      (node (ref "U2") (pin "5.GND") (pinfunction "(5)GND_5.GND") (pintype "bidirectional"))
      (node (ref "U3") (pin "20") (pinfunction "20.VSS_20") (pintype "bidirectional"))
      (node (ref "U4") (pin "1") (pinfunction "1.GND_1") (pintype "bidirectional"))
      (node (ref "U5") (pin "20.L") (pinfunction "20_20.L") (pintype "bidirectional"))
      (node (ref "U5") (pin "20.R") (pinfunction "20_20.R") (pintype "bidirectional"))
      (node (ref "U6") (pin "21") (pinfunction "GND_21") (pintype "power_in"))
      (node (ref "U6") (pin "3") (pinfunction "GND_2_3") (pintype "power_in"))
      (node (ref "U6") (pin "5") (pinfunction "GND_3_5") (pintype "power_in"))
      (node (ref "U7") (pin "5.GND") (pinfunction "(5)GND_5.GND") (pintype "bidirectional"))
      (node (ref "U8") (pin "1") (pinfunction "GND_1") (pintype "bidirectional"))
      (node (ref "U9") (pin "1") (pinfunction "GND_1") (pintype "bidirectional"))
    )
    (net (code "18") (name "ICSP_CLK") (class "Default")
      (node (ref "J1") (pin "5") (pinfunction "5.PGC_5") (pintype "bidirectional"))
      (node (ref "U3") (pin "18") (pinfunction "18.RA1/ICSPCLK_18") (pintype "bidirectional"))
      (node (ref "U5") (pin "18.L") (pinfunction "18_18.L") (pintype "bidirectional"))
      (node (ref "U5") (pin "18.R") (pinfunction "18_18.R") (pintype "bidirectional"))
    )
    (net (code "19") (name "ICSP_DAT") (class "Default")
      (node (ref "J1") (pin "4") (pinfunction "4.PGD_4") (pintype "bidirectional"))
      (node (ref "U3") (pin "19") (pinfunction "19.RA0/ICSPDAT_19") (pintype "bidirectional"))
      (node (ref "U5") (pin "19.L") (pinfunction "19_19.L") (pintype "bidirectional"))
      (node (ref "U5") (pin "19.R") (pinfunction "19_19.R") (pintype "bidirectional"))
    )
    (net (code "20") (name "MCLR") (class "Default")
      (node (ref "J1") (pin "1") (pinfunction "1.MCLR_1") (pintype "bidirectional"))
      (node (ref "R8") (pin "2") (pinfunction "2_2") (pintype "passive"))
      (node (ref "U3") (pin "4") (pinfunction "4.RA3/MCLR_4") (pintype "bidirectional"))
      (node (ref "U5") (pin "4.L") (pinfunction "4_4.L") (pintype "bidirectional"))
      (node (ref "U5") (pin "4.R") (pinfunction "4_4.R") (pintype "bidirectional"))
    )
    (net (code "21") (name "Net-(C4-+)") (class "Default")
      (node (ref "B1") (pin "3.B") (pinfunction "2_3.B") (pintype "bidirectional"))
      (node (ref "B1") (pin "4.B") (pinfunction "2_4.B") (pintype "bidirectional"))
      (node (ref "C4") (pin "1") (pinfunction "+_1") (pintype "passive"))
      (node (ref "R4") (pin "2") (pinfunction "2_2") (pintype "passive"))
      (node (ref "R5") (pin "2") (pinfunction "2_2") (pintype "passive"))
    )
    (net (code "22") (name "Net-(C6-+)") (class "Default")
      (node (ref "B2") (pin "3.B") (pinfunction "2_3.B") (pintype "bidirectional"))
      (node (ref "B2") (pin "4.B") (pinfunction "2_4.B") (pintype "bidirectional"))
      (node (ref "C6") (pin "1") (pinfunction "+_1") (pintype "passive"))
      (node (ref "R8") (pin "1") (pinfunction "1_1") (pintype "passive"))
      (node (ref "R9") (pin "2") (pinfunction "2_2") (pintype "passive"))
    )
    (net (code "23") (name "Net-(C11-+)") (class "Default")
      (node (ref "B3") (pin "3.B") (pinfunction "2_3.B") (pintype "bidirectional"))
      (node (ref "B3") (pin "4.B") (pinfunction "2_4.B") (pintype "bidirectional"))
      (node (ref "C11") (pin "1") (pinfunction "+_1") (pintype "passive"))
      (node (ref "R10") (pin "2") (pinfunction "2_2") (pintype "passive"))
      (node (ref "R11") (pin "2") (pinfunction "2_2") (pintype "passive"))
    )
    (net (code "24") (name "Net-(C13-+)") (class "Default")
      (node (ref "B4") (pin "3.B") (pinfunction "2_3.B") (pintype "bidirectional"))
      (node (ref "B4") (pin "4.B") (pinfunction "2_4.B") (pintype "bidirectional"))
      (node (ref "C13") (pin "1") (pinfunction "+_1") (pintype "passive"))
      (node (ref "R13") (pin "1") (pinfunction "1_1") (pintype "passive"))
      (node (ref "R14") (pin "2") (pinfunction "2_2") (pintype "passive"))
    )
    (net (code "25") (name "Net-(C15-+)") (class "Default")
      (node (ref "C15") (pin "1") (pinfunction "+_1") (pintype "passive"))
      (node (ref "U7") (pin "2.DTR") (pinfunction "(2)DTR_2.DTR") (pintype "bidirectional"))
    )
    (net (code "26") (name "Net-(J5-6.ADC3-Pad11)") (class "Default")
      (node (ref "J5") (pin "11") (pinfunction "6.ADC3_11") (pintype "bidirectional"))
      (node (ref "J5") (pin "6") (pinfunction "6.ADC3_6") (pintype "bidirectional"))
    )
    (net (code "27") (name "Net-(J5-7.ADC4-Pad10)") (class "Default")
      (node (ref "J5") (pin "10") (pinfunction "7.ADC4_10") (pintype "bidirectional"))
      (node (ref "J5") (pin "7") (pinfunction "7.ADC4_7") (pintype "bidirectional"))
    )
    (net (code "28") (name "Net-(J5-8.ADC5-Pad8)") (class "Default")
      (node (ref "J5") (pin "8") (pinfunction "8.ADC5_8") (pintype "bidirectional"))
      (node (ref "J5") (pin "9") (pinfunction "8.ADC5_9") (pintype "bidirectional"))
    )
    (net (code "29") (name "Net-(LED1-1.R-)") (class "Default")
      (node (ref "LED1") (pin "2") (pinfunction "1.R-_2") (pintype "passive"))
      (node (ref "R1") (pin "2") (pinfunction "2_2") (pintype "passive"))
    )
    (net (code "30") (name "Net-(LED1-2.G-)") (class "Default")
      (node (ref "LED1") (pin "3") (pinfunction "2.G-_3") (pintype "passive"))
      (node (ref "R2") (pin "2") (pinfunction "2_2") (pintype "passive"))
    )
    (net (code "31") (name "Net-(LED1-4.B-)") (class "Default")
      (node (ref "LED1") (pin "1") (pinfunction "4.B-_1") (pintype "passive"))
      (node (ref "R3") (pin "2") (pinfunction "2_2") (pintype "passive"))
    )
    (net (code "32") (name "Net-(LED2-PadA)") (class "Default")
      (node (ref "LED2") (pin "A") (pinfunction "A_A") (pintype "passive"))
      (node (ref "R12") (pin "2") (pinfunction "2_2") (pintype "passive"))
    )
    (net (code "33") (name "Net-(LED3-PadA)") (class "Default")
      (node (ref "LED3") (pin "A") (pinfunction "A_A") (pintype "passive"))
      (node (ref "R16") (pin "2") (pinfunction "2_2") (pintype "passive"))
    )
    (net (code "34") (name "PB0") (class "Default")
      (node (ref "J5") (pin "14") (pinfunction "3.ADC0_14") (pintype "bidirectional"))
      (node (ref "J5") (pin "3") (pinfunction "3.ADC0_3") (pintype "bidirectional"))
      (node (ref "U6") (pin "12") (pinfunction "PB0_12") (pintype "bidirectional"))
    )
    (net (code "35") (name "PB1") (class "Default")
      (node (ref "J5") (pin "13") (pinfunction "4.ADC1_13") (pintype "bidirectional"))
      (node (ref "J5") (pin "4") (pinfunction "4.ADC1_4") (pintype "bidirectional"))
      (node (ref "U6") (pin "13") (pinfunction "PB1_13") (pintype "bidirectional"))
    )
    (net (code "36") (name "PB2") (class "Default")
      (node (ref "J5") (pin "12") (pinfunction "5.ADC2_12") (pintype "bidirectional"))
      (node (ref "J5") (pin "5") (pinfunction "5.ADC2_5") (pintype "bidirectional"))
      (node (ref "U6") (pin "14") (pinfunction "PB2_14") (pintype "bidirectional"))
    )
    (net (code "37") (name "PC0") (class "Default")
      (node (ref "J6") (pin "11") (pinfunction "6.ADC3_11") (pintype "bidirectional"))
      (node (ref "J6") (pin "6") (pinfunction "6.ADC3_6") (pintype "bidirectional"))
      (node (ref "U6") (pin "23") (pinfunction "PC0_23") (pintype "bidirectional"))
    )
    (net (code "38") (name "PC1") (class "Default")
      (node (ref "J6") (pin "12") (pinfunction "5.ADC2_12") (pintype "bidirectional"))
      (node (ref "J6") (pin "5") (pinfunction "5.ADC2_5") (pintype "bidirectional"))
      (node (ref "U6") (pin "24") (pinfunction "PC1_24") (pintype "bidirectional"))
    )
    (net (code "39") (name "PC2") (class "Default")
      (node (ref "J6") (pin "13") (pinfunction "4.ADC1_13") (pintype "bidirectional"))
      (node (ref "J6") (pin "4") (pinfunction "4.ADC1_4") (pintype "bidirectional"))
      (node (ref "U6") (pin "25") (pinfunction "PC2_25") (pintype "bidirectional"))
    )
    (net (code "40") (name "PC3") (class "Default")
      (node (ref "J6") (pin "14") (pinfunction "3.ADC0_14") (pintype "bidirectional"))
      (node (ref "J6") (pin "3") (pinfunction "3.ADC0_3") (pintype "bidirectional"))
      (node (ref "U6") (pin "26") (pinfunction "PC3_26") (pintype "bidirectional"))
    )
    (net (code "41") (name "PD2") (class "Default")
      (node (ref "J4") (pin "14") (pinfunction "3.ADC0_14") (pintype "bidirectional"))
      (node (ref "J4") (pin "3") (pinfunction "3.ADC0_3") (pintype "bidirectional"))
      (node (ref "U6") (pin "32") (pinfunction "PD2_32") (pintype "bidirectional"))
    )
    (net (code "42") (name "PD3") (class "Default")
      (node (ref "J4") (pin "13") (pinfunction "4.ADC1_13") (pintype "bidirectional"))
      (node (ref "J4") (pin "4") (pinfunction "4.ADC1_4") (pintype "bidirectional"))
      (node (ref "U6") (pin "1") (pinfunction "PD3_1") (pintype "bidirectional"))
    )
    (net (code "43") (name "PD4") (class "Default")
      (node (ref "J4") (pin "12") (pinfunction "5.ADC2_12") (pintype "bidirectional"))
      (node (ref "J4") (pin "5") (pinfunction "5.ADC2_5") (pintype "bidirectional"))
      (node (ref "R10") (pin "1") (pinfunction "1_1") (pintype "passive"))
      (node (ref "U6") (pin "2") (pinfunction "PD4_2") (pintype "bidirectional"))
    )
    (net (code "44") (name "PD5") (class "Default")
      (node (ref "J4") (pin "11") (pinfunction "6.ADC3_11") (pintype "bidirectional"))
      (node (ref "J4") (pin "6") (pinfunction "6.ADC3_6") (pintype "bidirectional"))
      (node (ref "U6") (pin "9") (pinfunction "PD5_9") (pintype "bidirectional"))
    )
    (net (code "45") (name "PD6") (class "Default")
      (node (ref "J4") (pin "10") (pinfunction "7.ADC4_10") (pintype "bidirectional"))
      (node (ref "J4") (pin "7") (pinfunction "7.ADC4_7") (pintype "bidirectional"))
      (node (ref "U6") (pin "10") (pinfunction "PD6_10") (pintype "bidirectional"))
    )
    (net (code "46") (name "PD7") (class "Default")
      (node (ref "J4") (pin "8") (pinfunction "8.ADC5_8") (pintype "bidirectional"))
      (node (ref "J4") (pin "9") (pinfunction "8.ADC5_9") (pintype "bidirectional"))
      (node (ref "U6") (pin "11") (pinfunction "PD7_11") (pintype "bidirectional"))
    )
    (net (code "47") (name "PIC-USB-3V3") (class "Default")
      (node (ref "D3") (pin "A") (pinfunction "A_A") (pintype "passive"))
      (node (ref "U2") (pin "1.3V3") (pinfunction "(1)3V3_1.3V3") (pintype "bidirectional"))
    )
    (net (code "48") (name "PIC-USB-5V") (class "Default")
      (node (ref "D6") (pin "A") (pinfunction "A_A") (pintype "passive"))
      (node (ref "U2") (pin "6.5V") (pinfunction "(6)5V_6.5V") (pintype "bidirectional"))
    )
    (net (code "49") (name "RA2") (class "Default")
      (node (ref "R3") (pin "1") (pinfunction "1_1") (pintype "passive"))
      (node (ref "U3") (pin "17") (pinfunction "17.RA2_17") (pintype "bidirectional"))
      (node (ref "U5") (pin "17.L") (pinfunction "17_17.L") (pintype "bidirectional"))
      (node (ref "U5") (pin "17.R") (pinfunction "17_17.R") (pintype "bidirectional"))
    )
    (net (code "50") (name "RA4") (class "Default")
      (node (ref "U1") (pin "1") (pinfunction "1_1") (pintype "bidirectional"))
      (node (ref "U3") (pin "3") (pinfunction "3.RA4_3") (pintype "bidirectional"))
      (node (ref "U5") (pin "3.L") (pinfunction "3_3.L") (pintype "bidirectional"))
      (node (ref "U5") (pin "3.R") (pinfunction "3_3.R") (pintype "bidirectional"))
    )
    (net (code "51") (name "RA5") (class "Default")
      (node (ref "R2") (pin "1") (pinfunction "1_1") (pintype "passive"))
      (node (ref "U3") (pin "2") (pinfunction "2.RA5_2") (pintype "bidirectional"))
      (node (ref "U5") (pin "2.L") (pinfunction "2_2.L") (pintype "bidirectional"))
      (node (ref "U5") (pin "2.R") (pinfunction "2_2.R") (pintype "bidirectional"))
    )
    (net (code "52") (name "RB5") (class "Default")
      (node (ref "J2") (pin "5") (pinfunction "5.ADC2_5") (pintype "bidirectional"))
      (node (ref "U3") (pin "12") (pinfunction "12.RB5_12") (pintype "bidirectional"))
      (node (ref "U5") (pin "12.L") (pinfunction "12_12.L") (pintype "bidirectional"))
      (node (ref "U5") (pin "12.R") (pinfunction "12_12.R") (pintype "bidirectional"))
    )
    (net (code "53") (name "RB7") (class "Default")
      (node (ref "R4") (pin "1") (pinfunction "1_1") (pintype "passive"))
      (node (ref "U3") (pin "10") (pinfunction "10.RB7_10") (pintype "bidirectional"))
      (node (ref "U5") (pin "10.L") (pinfunction "10_10.L") (pintype "bidirectional"))
      (node (ref "U5") (pin "10.R") (pinfunction "10_10.R") (pintype "bidirectional"))
    )
    (net (code "54") (name "RC0") (class "Default")
      (node (ref "U1") (pin "4") (pinfunction "4_4") (pintype "bidirectional"))
      (node (ref "U3") (pin "16") (pinfunction "16.RC0_16") (pintype "bidirectional"))
      (node (ref "U5") (pin "16.L") (pinfunction "16_16.L") (pintype "bidirectional"))
      (node (ref "U5") (pin "16.R") (pinfunction "16_16.R") (pintype "bidirectional"))
    )
    (net (code "55") (name "RC1") (class "Default")
      (node (ref "U1") (pin "3") (pinfunction "3_3") (pintype "bidirectional"))
      (node (ref "U3") (pin "15") (pinfunction "15.RC1_15") (pintype "bidirectional"))
      (node (ref "U5") (pin "15.L") (pinfunction "15_15.L") (pintype "bidirectional"))
      (node (ref "U5") (pin "15.R") (pinfunction "15_15.R") (pintype "bidirectional"))
    )
    (net (code "56") (name "RC2") (class "Default")
      (node (ref "J2") (pin "3") (pinfunction "3.ADC0_3") (pintype "bidirectional"))
      (node (ref "U3") (pin "14") (pinfunction "14.RC2_14") (pintype "bidirectional"))
      (node (ref "U5") (pin "14.L") (pinfunction "14_14.L") (pintype "bidirectional"))
      (node (ref "U5") (pin "14.R") (pinfunction "14_14.R") (pintype "bidirectional"))
    )
    (net (code "57") (name "RC3") (class "Default")
      (node (ref "J2") (pin "4") (pinfunction "4.ADC1_4") (pintype "bidirectional"))
      (node (ref "U3") (pin "7") (pinfunction "7.RC3_7") (pintype "bidirectional"))
      (node (ref "U5") (pin "7.L") (pinfunction "7_7.L") (pintype "bidirectional"))
      (node (ref "U5") (pin "7.R") (pinfunction "7_7.R") (pintype "bidirectional"))
    )
    (net (code "58") (name "RC4") (class "Default")
      (node (ref "U2") (pin "3.RXI") (pinfunction "(3)MCU.TX_3.RXI") (pintype "bidirectional"))
      (node (ref "U3") (pin "6") (pinfunction "6.RC4_6") (pintype "bidirectional"))
      (node (ref "U5") (pin "6.L") (pinfunction "6_6.L") (pintype "bidirectional"))
      (node (ref "U5") (pin "6.R") (pinfunction "6_6.R") (pintype "bidirectional"))
    )
    (net (code "59") (name "RC5") (class "Default")
      (node (ref "U2") (pin "4.RDO") (pinfunction "(4)MCU.RX_4.RDO") (pintype "bidirectional"))
      (node (ref "U3") (pin "5") (pinfunction "5.RC5_5") (pintype "bidirectional"))
      (node (ref "U5") (pin "5.L") (pinfunction "5_5.L") (pintype "bidirectional"))
      (node (ref "U5") (pin "5.R") (pinfunction "5_5.R") (pintype "bidirectional"))
    )
    (net (code "60") (name "RC6") (class "Default")
      (node (ref "R1") (pin "1") (pinfunction "1_1") (pintype "passive"))
      (node (ref "U3") (pin "8") (pinfunction "8.RC6_8") (pintype "bidirectional"))
      (node (ref "U5") (pin "8.L") (pinfunction "8_8.L") (pintype "bidirectional"))
      (node (ref "U5") (pin "8.R") (pinfunction "8_8.R") (pintype "bidirectional"))
    )
    (net (code "61") (name "RC7") (class "Default")
      (node (ref "U1") (pin "2") (pinfunction "2_2") (pintype "bidirectional"))
      (node (ref "U3") (pin "9") (pinfunction "9.RC7_9") (pintype "bidirectional"))
      (node (ref "U5") (pin "9.L") (pinfunction "9_9.L") (pintype "bidirectional"))
      (node (ref "U5") (pin "9.R") (pinfunction "9_9.R") (pintype "bidirectional"))
    )
    (net (code "62") (name "SCL") (class "Default")
      (node (ref "$3_73_$") (pin "3.SCL") (pinfunction "3.SCL_3.SCL") (pintype "bidirectional"))
      (node (ref "R7") (pin "2") (pinfunction "2_2") (pintype "passive"))
      (node (ref "U3") (pin "11") (pinfunction "11.RB6_11") (pintype "bidirectional"))
      (node (ref "U4") (pin "4") (pinfunction "4.SCL_4") (pintype "bidirectional"))
      (node (ref "U5") (pin "11.L") (pinfunction "11_11.L") (pintype "bidirectional"))
      (node (ref "U5") (pin "11.R") (pinfunction "11_11.R") (pintype "bidirectional"))
      (node (ref "U6") (pin "28") (pinfunction "PC5_28") (pintype "bidirectional"))
    )
    (net (code "63") (name "SDA") (class "Default")
      (node (ref "$3_73_$") (pin "4.SDA") (pinfunction "4.SDA_4.SDA") (pintype "bidirectional"))
      (node (ref "R6") (pin "2") (pinfunction "2_2") (pintype "passive"))
      (node (ref "U3") (pin "13") (pinfunction "13.RB4_13") (pintype "bidirectional"))
      (node (ref "U4") (pin "3") (pinfunction "3.SDA_3") (pintype "bidirectional"))
      (node (ref "U5") (pin "13.L") (pinfunction "13_13.L") (pintype "bidirectional"))
      (node (ref "U5") (pin "13.R") (pinfunction "13_13.R") (pintype "bidirectional"))
      (node (ref "U6") (pin "27") (pinfunction "PC4_27") (pintype "bidirectional"))
    )
    (net (code "64") (name "UNREG_IN") (class "Default")
      (node (ref "D1") (pin "A") (pinfunction "A_A") (pintype "passive"))
      (node (ref "J7") (pin "TIP") (pinfunction "TIP_TIP") (pintype "bidirectional"))
    )
    (net (code "65") (name "UNREG_IN_POLARITY_PROTECTED") (class "Default")
      (node (ref "C18") (pin "1") (pinfunction "+_1") (pintype "passive"))
      (node (ref "C19") (pin "1") (pinfunction "+_1") (pintype "passive"))
      (node (ref "C20") (pin "1") (pinfunction "+_1") (pintype "passive"))
      (node (ref "C21") (pin "1") (pinfunction "+_1") (pintype "passive"))
      (node (ref "D1") (pin "C") (pinfunction "C_C") (pintype "passive"))
      (node (ref "U8") (pin "3") (pinfunction "IN_3") (pintype "bidirectional"))
      (node (ref "U9") (pin "3") (pinfunction "IN_3") (pintype "bidirectional"))
    )
    (net (code "66") (name "VDD") (class "Default")
      (node (ref "$3_73_$") (pin "2.VDD") (pinfunction "1.VDD_2.VDD") (pintype "bidirectional"))
      (node (ref "C1") (pin "1") (pinfunction "+_1") (pintype "passive"))
      (node (ref "C10") (pin "1") (pinfunction "+_1") (pintype "passive"))
      (node (ref "C16") (pin "1") (pinfunction "+_1") (pintype "passive"))
      (node (ref "C17") (pin "1") (pinfunction "+_1") (pintype "passive"))
      (node (ref "C2") (pin "1") (pinfunction "+_1") (pintype "passive"))
      (node (ref "C3") (pin "1") (pinfunction "+_1") (pintype "passive"))
      (node (ref "C5") (pin "1") (pinfunction "+_1") (pintype "passive"))
      (node (ref "C9") (pin "1") (pinfunction "+_1") (pintype "passive"))
      (node (ref "J1") (pin "2") (pinfunction "2.VDD(PWR)_2") (pintype "bidirectional"))
      (node (ref "J2") (pin "2") (pinfunction "2.VDD_2") (pintype "bidirectional"))
      (node (ref "J3") (pin "2") (pinfunction "2_2") (pintype "bidirectional"))
      (node (ref "J4") (pin "15") (pinfunction "2.VDD_15") (pintype "bidirectional"))
      (node (ref "J4") (pin "2") (pinfunction "2.VDD_2") (pintype "bidirectional"))
      (node (ref "J5") (pin "15") (pinfunction "2.VDD_15") (pintype "bidirectional"))
      (node (ref "J5") (pin "2") (pinfunction "2.VDD_2") (pintype "bidirectional"))
      (node (ref "J6") (pin "15") (pinfunction "2.VDD_15") (pintype "bidirectional"))
      (node (ref "J6") (pin "2") (pinfunction "2.VDD_2") (pintype "bidirectional"))
      (node (ref "J8") (pin "2") (pinfunction "2_2") (pintype "bidirectional"))
      (node (ref "LED1") (pin "4") (pinfunction "3.+_4") (pintype "passive"))
      (node (ref "R11") (pin "1") (pinfunction "1_1") (pintype "passive"))
      (node (ref "R14") (pin "1") (pinfunction "1_1") (pintype "passive"))
      (node (ref "R15") (pin "1") (pinfunction "1_1") (pintype "passive"))
      (node (ref "R16") (pin "1") (pinfunction "1_1") (pintype "passive"))
      (node (ref "R5") (pin "1") (pinfunction "1_1") (pintype "passive"))
      (node (ref "R6") (pin "1") (pinfunction "1_1") (pintype "passive"))
      (node (ref "R7") (pin "1") (pinfunction "1_1") (pintype "passive"))
      (node (ref "R9") (pin "1") (pinfunction "1_1") (pintype "passive"))
      (node (ref "U3") (pin "1") (pinfunction "1.VDD_1") (pintype "bidirectional"))
      (node (ref "U4") (pin "2") (pinfunction "2.VDD_2") (pintype "bidirectional"))
      (node (ref "U5") (pin "1.L") (pinfunction "1_1.L") (pintype "bidirectional"))
      (node (ref "U5") (pin "1.R") (pinfunction "1_1.R") (pintype "bidirectional"))
      (node (ref "U6") (pin "4") (pinfunction "VCC_2_4") (pintype "power_in"))
      (node (ref "U6") (pin "6") (pinfunction "VCC_6") (pintype "power_in"))
    )
    (net (code "67") (name "XTAL1") (class "Default")
      (node (ref "C7") (pin "2") (pinfunction "+_2") (pintype "passive"))
      (node (ref "U6") (pin "7") (pinfunction "PB6_7") (pintype "bidirectional"))
      (node (ref "Y1") (pin "3") (pinfunction "2_3") (pintype "bidirectional"))
    )
    (net (code "68") (name "XTAL2") (class "Default")
      (node (ref "C8") (pin "2") (pinfunction "+_2") (pintype "passive"))
      (node (ref "U6") (pin "8") (pinfunction "PB7_8") (pintype "bidirectional"))
      (node (ref "Y1") (pin "1") (pinfunction "1_1") (pintype "bidirectional"))
    )
    (net (code "69") (name "unconnected-(J1-6.PGM-Pad6)") (class "Default")
      (node (ref "J1") (pin "6") (pinfunction "6.PGM_6") (pintype "bidirectional"))
    )
    (net (code "70") (name "unconnected-(J7-PadRING_SW)") (class "Default")
      (node (ref "J7") (pin "RING_SW") (pinfunction "RING_SW_RING_SW") (pintype "bidirectional"))
    )
    (net (code "71") (name "unconnected-(U2-(2)DTR-Pad2.DTR)") (class "Default")
      (node (ref "U2") (pin "2.DTR") (pinfunction "(2)DTR_2.DTR") (pintype "bidirectional"))
    )
  )
)
